# Sheet1.net
KiCad netlist of a schematic drawn in Altium Designer
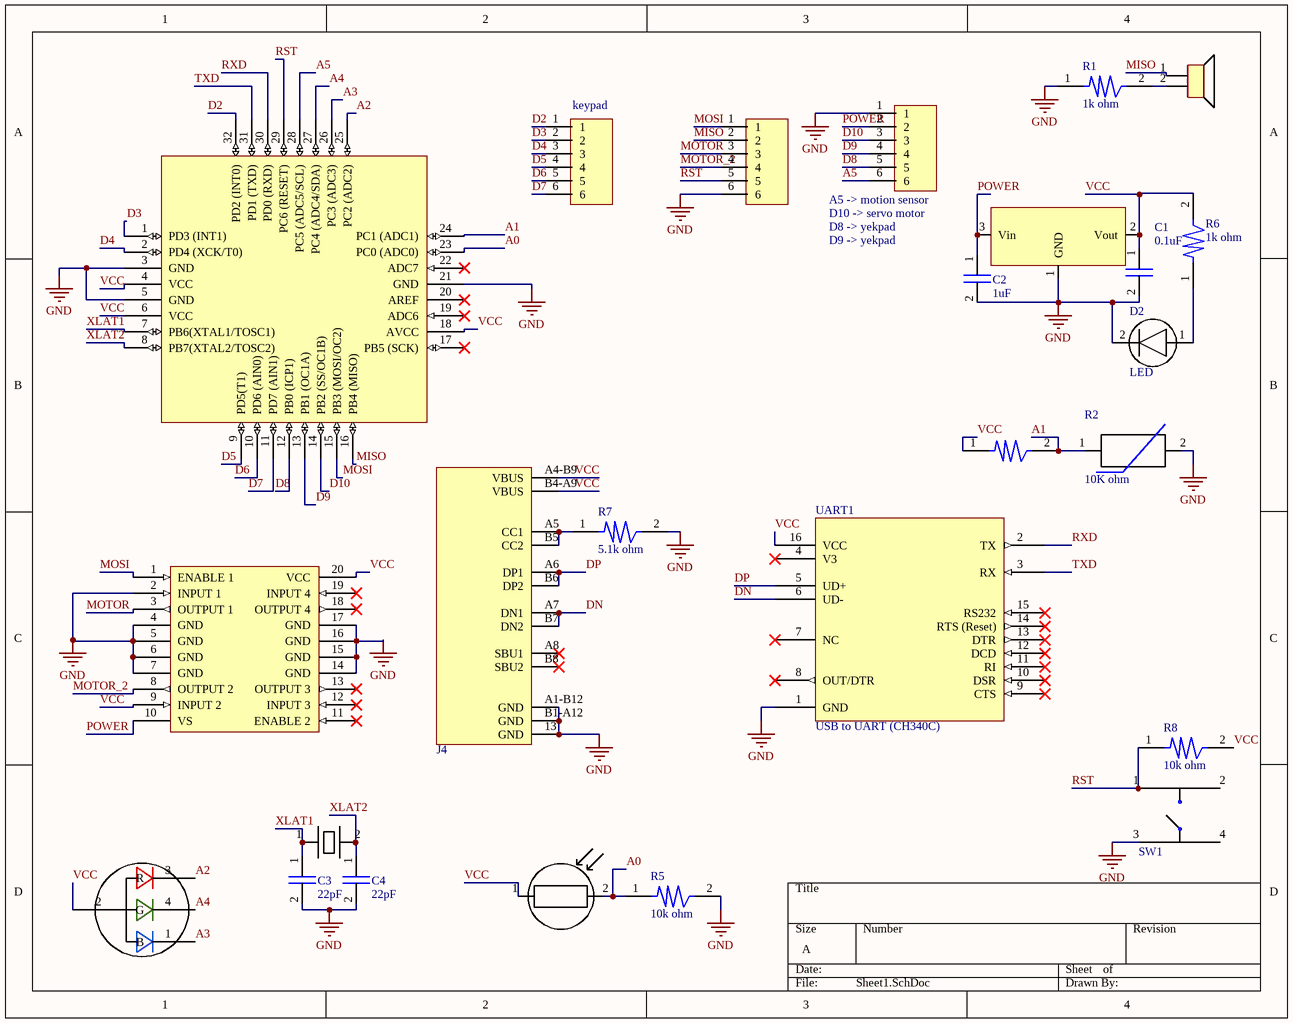
[diagram p0: Sheet1.SchDoc]

(export (version "E")
  (design (tool "Eeschema 10.0.6"))
  (components
    (comp (ref "BUZ1")
      (value "Buzzer")
      (footprint "Buzzer")
      (fields (field (name "MANUFACTURER") "Murata Electronics"))
      (libsource (lib "SCHLibrary-Badr") (part "Buzzer"))
    )
    (comp (ref "C1")
      (value "0.1uF")
      (footprint "Capacitor 0603 SMD")
      (description "50V 100nF X7R ±10% 0603 Multilayer Ceramic Capacitors MLCC - SMD/SMT ROHS")
      (fields (field (name "MANUFACTURER") "YAGEO"))
      (libsource (lib "SCHLibrary-Badr") (part "Capacitor 0.1uF"))
    )
    (comp (ref "C2")
      (value "1uF")
      (footprint "Capacitor 0603 SMD")
      (description "16V 1uF X5R ±10% 0603 Multilayer Ceramic Capacitors MLCC - SMD/SMT ROHS")
      (fields (field (name "MANUFACTURER") "Samsung Electro-Mechanics"))
      (libsource (lib "SCHLibrary-Badr") (part "Capacitor 1uF"))
    )
    (comp (ref "C3")
      (value "22pF")
      (footprint "Capacitor 0603 SMD")
      (description "50V 22pF NP0 ±5% 0603 Multilayer Ceramic Capacitors MLCC - SMD/SMT ROHS")
      (fields (field (name "MANUFACTURER") "YAGEO"))
      (libsource (lib "SCHLibrary-Badr") (part "Capacitor 22pF"))
    )
    (comp (ref "C4")
      (value "22pF")
      (footprint "Capacitor 0603 SMD")
      (description "50V 22pF NP0 ±5% 0603 Multilayer Ceramic Capacitors MLCC - SMD/SMT ROHS")
      (fields (field (name "MANUFACTURER") "YAGEO"))
      (libsource (lib "SCHLibrary-Badr") (part "Capacitor 22pF"))
    )
    (comp (ref "D1")
      (value "RGB")
      (footprint "RGB")
      (description "SMD,1.5x3mm RGB LEDs ROHS")
      (fields (field (name "MANUFACTURER") "MEIHUA") (field (name "MFR. PART #") "MHS110RGBCT"))
      (libsource (lib "Schlib_N") (part "RGB"))
    )
    (comp (ref "D2")
      (value "LED")
      (footprint "LED")
      (description "360mcd 515nm~530nm Emerald 1206 LED Indication - Discrete ROHS")
      (fields
        (field (name "MANUFACTURER") "Everlight Elec")
        (field (name "MFR. PART #") "15-21/GHC-XS1T1/3T")
      )
      (libsource (lib "Schlib_N") (part "LED"))
    )
    (comp (ref "J1")
      (value "6P 2mm Pin Headers")
      (footprint "6P 2mm Pin header")
      (description "Connector Header Through Hole 6 position 0.079\" (2.00mm)")
      (fields
        (field (name "MANUFACTURER") "TE Connectivity AMP Connectors")
        (field (name "MANUFACTURER PART NUMBER") "2355172-6")
      )
      (libsource (lib "SCHLibrary-Badr") (part "6P 2mm Pin Headers"))
    )
    (comp (ref "J2")
      (value "6P 2mm Pin Headers")
      (footprint "6P 2mm Pin header")
      (description "Connector Header Through Hole 6 position 0.079\" (2.00mm)")
      (fields
        (field (name "MANUFACTURER") "TE Connectivity AMP Connectors")
        (field (name "MANUFACTURER PART NUMBER") "2355172-6")
      )
      (libsource (lib "SCHLibrary-Badr") (part "6P 2mm Pin Headers"))
    )
    (comp (ref "J3")
      (value "6P 2mm Pin Headers")
      (footprint "6P 2mm Pin header")
      (description "Connector Header Through Hole 6 position 0.079\" (2.00mm)")
      (fields
        (field (name "MANUFACTURER") "TE Connectivity AMP Connectors")
        (field (name "MANUFACTURER PART NUMBER") "2355172-6")
      )
      (libsource (lib "SCHLibrary-Badr") (part "6P 2mm Pin Headers"))
    )
    (comp (ref "J4")
      (value "TYPE-C-31-M-12")
      (footprint "USB TYPE C-31-M-12")
      (description "5A 1 16P Female Type-C SMD USB Connectors ROHS")
      (fields (field (name "MANUFACTURER") "Korean Hroparts Elec"))
      (libsource (lib "SCHLibrary-Badr") (part "TYPE-C-31-M-12"))
    )
    (comp (ref "R1")
      (value "1k ohm")
      (footprint "Resistor 0603 SMD")
      (description "100mW Thick Film Resistors 75V ±100ppm/℃ ±1% 1kΩ 0603 Chip Resistor - Surface Mount ROHS")
      (fields (field (name "MANUFACTURER") "UNI-ROYAL(Uniroyal Elec)"))
      (libsource (lib "SCHLibrary-Badr") (part "Resistor 1k Ohm"))
    )
    (comp (ref "R2")
      (value "10K ohm")
      (footprint "Resistor 0603 SMD")
      (description "THERMISTOR NTC 10KOHM 4250K 0603")
      (fields (field (name "MANUFACTURER") "Panasonic Electronic Components"))
      (libsource (lib "SCHLibrary-Badr") (part "NTC Thermo (ERT-J1VR103J)"))
    )
    (comp (ref "R3")
      (value "10k ohm")
      (footprint "Resistor 0603 SMD")
      (description "100mW Thick Film Resistors 75V ±100ppm/℃ ±1% 10kΩ 0603 Chip Resistor - Surface Mount ROHS")
      (fields (field (name "MANUFACTURER") "UNI-ROYAL(Uniroyal Elec)"))
      (libsource (lib "SCHLibrary-Badr") (part "Resistor 10k Ohm"))
    )
    (comp (ref "R4")
      (value "Photoresistors 8kΩ~20kΩ")
      (footprint "Photoresistor GL5528")
      (description "8kΩ~20kΩ 540nm 1MΩ Plugin,P=3mm Photoresistors ROHS")
      (fields (field (name "MANUFACTURER") "Senba Sensing Tech"))
      (libsource (lib "SCHLibrary-Badr") (part "Photoresistors 8kΩ~20kΩ"))
    )
    (comp (ref "R5")
      (value "10k ohm")
      (footprint "Resistor 0603 SMD")
      (description "100mW Thick Film Resistors 75V ±100ppm/℃ ±1% 10kΩ 0603 Chip Resistor - Surface Mount ROHS")
      (fields (field (name "MANUFACTURER") "UNI-ROYAL(Uniroyal Elec)"))
      (libsource (lib "SCHLibrary-Badr") (part "Resistor 10k Ohm"))
    )
    (comp (ref "R6")
      (value "1k ohm")
      (footprint "Resistor 0603 SMD")
      (description "100mW Thick Film Resistors 75V ±100ppm/℃ ±1% 1kΩ 0603 Chip Resistor - Surface Mount ROHS")
      (fields (field (name "MANUFACTURER") "UNI-ROYAL(Uniroyal Elec)"))
      (libsource (lib "SCHLibrary-Badr") (part "Resistor 1k Ohm"))
    )
    (comp (ref "R7")
      (value "5.1k ohm")
      (footprint "Resistor 0603 SMD")
      (description "100mW Thick Film Resistors 75V ±100ppm/℃ ±1% 5.1kΩ 0603 Chip Resistor - Surface Mount ROHS")
      (fields (field (name "MANUFACTURER") "UNI-ROYAL(Uniroyal Elec)"))
      (libsource (lib "SCHLibrary-Badr") (part "Resistor 5.1k Ohm"))
    )
    (comp (ref "R8")
      (value "10k ohm")
      (footprint "Resistor 0603 SMD")
      (description "100mW Thick Film Resistors 75V ±100ppm/℃ ±1% 10kΩ 0603 Chip Resistor - Surface Mount ROHS")
      (fields (field (name "MANUFACTURER") "UNI-ROYAL(Uniroyal Elec)"))
      (libsource (lib "SCHLibrary-Badr") (part "Resistor 10k Ohm"))
    )
    (comp (ref "SW1")
      (value "Tact Switch")
      (footprint "Tact Switch")
      (description "SWITCH TACTILE SPST-NO 0.05A 12V\r\nTactile Switch SPST-NO Top Actuated Surface Mount")
      (fields (field (name "MANUFACTURER") "C&K"))
      (libsource (lib "SCHLibrary-Badr") (part "Tact Switch"))
    )
    (comp (ref "U1")
      (value "Motor_Driver")
      (footprint "L293D")
      (description "SOIC-20-300mil Stepper Motor Driver ROHS")
      (fields (field (name "MANUFACTURER") "STMicroelectronics") (field (name "MFR. PART #") "L293DD013TR"))
      (libsource (lib "Schlib_N") (part "L293D"))
    )
    (comp (ref "U2")
      (value "ATmega 8A")
      (footprint "ATmega 8A")
      (description "8KB 1KB FLASH 23 2.7V~5.5V AVR 16MHz TQFP-32(7x7) Microcontrollers (MCU/MPU/SOC) ROHS")
      (fields (field (name "MANUFACTURER") "Microchip Tech") (field (name "MFR. PART #") "ATMEGA8A-AU"))
      (libsource (lib "Schlib_N") (part "ATmega 8A"))
    )
    (comp (ref "UART1")
      (value "USB to UART (CH340C)")
      (footprint "(USB-UART) CH340C")
      (description "2Mbps Transceiver USB 2.0 SOP-16 USB Converters ROHS")
      (fields (field (name "MANUFACTURER") "WCH(Jiangsu Qin Heng)"))
      (libsource (lib "SCHLibrary-Badr") (part "USB to UART (CH340C)"))
    )
    (comp (ref "VR1")
      (value "Regulator 5V")
      (footprint "Regulator 5V AMS1117")
      (fields (field (name "MANUFACTURER") "MSKSEMI"))
      (libsource (lib "SCHLibrary-Badr") (part "Regulator 5V"))
    )
    (comp (ref "Y1")
      (value "Crystal 16Mhz")
      (footprint "Crystal 16Mhz")
      (description "16 MHz ±30ppm Crystal 20pF 50 Ohms HC-49/US")
      (fields (field (name "MANUFACTURER") "ECS Inc."))
      (libsource (lib "SCHLibrary-Badr") (part "Crystal 16Mhz"))
    )
  )
  (nets
    (net (code "1") (name "/A0") (class "Default")
      (node (ref "R4") (pin "2") (pinfunction "2_2") (pintype "passive"))
      (node (ref "R5") (pin "1") (pinfunction "1_1") (pintype "passive"))
      (node (ref "U2") (pin "23") (pinfunction "PC0_(ADC0)_23") (pintype "bidirectional"))
    )
    (net (code "2") (name "/A1") (class "Default")
      (node (ref "R2") (pin "1") (pinfunction "1_1") (pintype "passive"))
      (node (ref "R3") (pin "2") (pinfunction "2_2") (pintype "passive"))
      (node (ref "U2") (pin "24") (pinfunction "PC1_(ADC1)_24") (pintype "bidirectional"))
    )
    (net (code "3") (name "/A2") (class "Default")
      (node (ref "D1") (pin "3") (pinfunction "R_3") (pintype "passive"))
      (node (ref "U2") (pin "25") (pinfunction "PC2_(ADC2)_25") (pintype "bidirectional"))
    )
    (net (code "4") (name "/A3") (class "Default")
      (node (ref "D1") (pin "1") (pinfunction "B_1") (pintype "passive"))
      (node (ref "U2") (pin "26") (pinfunction "PC3_(ADC3)_26") (pintype "bidirectional"))
    )
    (net (code "5") (name "/A4") (class "Default")
      (node (ref "D1") (pin "4") (pinfunction "G_4") (pintype "passive"))
      (node (ref "U2") (pin "27") (pinfunction "PC4_(ADC4/SDA)_27") (pintype "bidirectional"))
    )
    (net (code "6") (name "/A5") (class "Default")
      (node (ref "J1") (pin "6") (pinfunction "6_6") (pintype "passive"))
      (node (ref "U2") (pin "28") (pinfunction "PC5_(ADC5/SCL)_28") (pintype "bidirectional"))
    )
    (net (code "7") (name "/D2") (class "Default")
      (node (ref "J3") (pin "1") (pinfunction "1_1") (pintype "passive"))
      (node (ref "U2") (pin "32") (pinfunction "PD2_(INT0)_32") (pintype "bidirectional"))
    )
    (net (code "8") (name "/D3") (class "Default")
      (node (ref "J3") (pin "2") (pinfunction "2_2") (pintype "passive"))
      (node (ref "U2") (pin "1") (pinfunction "PD3_(INT1)_1") (pintype "bidirectional"))
    )
    (net (code "9") (name "/D4") (class "Default")
      (node (ref "J3") (pin "3") (pinfunction "3_3") (pintype "passive"))
      (node (ref "U2") (pin "2") (pinfunction "PD4_(XCK/T0)_2") (pintype "bidirectional"))
    )
    (net (code "10") (name "/D5") (class "Default")
      (node (ref "J3") (pin "4") (pinfunction "4_4") (pintype "passive"))
      (node (ref "U2") (pin "9") (pinfunction "PD5(T1)_9") (pintype "bidirectional"))
    )
    (net (code "11") (name "/D6") (class "Default")
      (node (ref "J3") (pin "5") (pinfunction "5_5") (pintype "passive"))
      (node (ref "U2") (pin "10") (pinfunction "PD6_(AIN0)_10") (pintype "bidirectional"))
    )
    (net (code "12") (name "/D7") (class "Default")
      (node (ref "J3") (pin "6") (pinfunction "6_6") (pintype "passive"))
      (node (ref "U2") (pin "11") (pinfunction "PD7_(AIN1)_11") (pintype "bidirectional"))
    )
    (net (code "13") (name "/D8") (class "Default")
      (node (ref "J1") (pin "5") (pinfunction "5_5") (pintype "passive"))
      (node (ref "U2") (pin "12") (pinfunction "PB0_(ICP1)_12") (pintype "bidirectional"))
    )
    (net (code "14") (name "/D9") (class "Default")
      (node (ref "J1") (pin "4") (pinfunction "4_4") (pintype "passive"))
      (node (ref "U2") (pin "13") (pinfunction "PB1_(OC1A)_13") (pintype "bidirectional"))
    )
    (net (code "15") (name "/D10") (class "Default")
      (node (ref "J1") (pin "3") (pinfunction "3_3") (pintype "passive"))
      (node (ref "U2") (pin "14") (pinfunction "PB2_(SS/OC1B)_14") (pintype "bidirectional"))
    )
    (net (code "16") (name "/DN") (class "Default")
      (node (ref "J4") (pin "A7") (pinfunction "DN1_A7") (pintype "passive"))
      (node (ref "J4") (pin "B7") (pinfunction "DN2_B7") (pintype "passive"))
      (node (ref "UART1") (pin "6") (pinfunction "UD-_6") (pintype "passive"))
    )
    (net (code "17") (name "/DP") (class "Default")
      (node (ref "J4") (pin "A6") (pinfunction "DP1_A6") (pintype "passive"))
      (node (ref "J4") (pin "B6") (pinfunction "DP2_B6") (pintype "passive"))
      (node (ref "UART1") (pin "5") (pinfunction "UD+_5") (pintype "passive"))
    )
    (net (code "18") (name "/MISO") (class "Default")
      (node (ref "BUZ1") (pin "1") (pinfunction "1_1") (pintype "passive"))
      (node (ref "J2") (pin "2") (pinfunction "2_2") (pintype "passive"))
      (node (ref "U2") (pin "16") (pinfunction "PB4_(MISO)_16") (pintype "bidirectional"))
    )
    (net (code "19") (name "/MOSI") (class "Default")
      (node (ref "J2") (pin "1") (pinfunction "1_1") (pintype "passive"))
      (node (ref "U1") (pin "1") (pinfunction "ENABLE_1_1") (pintype "input"))
      (node (ref "U2") (pin "15") (pinfunction "PB3_(MOSI/OC2)_15") (pintype "bidirectional"))
    )
    (net (code "20") (name "/MOTOR") (class "Default")
      (node (ref "J2") (pin "3") (pinfunction "3_3") (pintype "passive"))
      (node (ref "U1") (pin "3") (pinfunction "OUTPUT_1_3") (pintype "output"))
    )
    (net (code "21") (name "/MOTOR_2") (class "Default")
      (node (ref "J2") (pin "4") (pinfunction "4_4") (pintype "passive"))
      (node (ref "U1") (pin "8") (pinfunction "OUTPUT_2_8") (pintype "output"))
    )
    (net (code "22") (name "/POWER") (class "Default")
      (node (ref "C2") (pin "1") (pinfunction "1_1") (pintype "passive"))
      (node (ref "J1") (pin "2") (pinfunction "2_2") (pintype "passive"))
      (node (ref "U1") (pin "10") (pinfunction "VS_10") (pintype "passive"))
      (node (ref "VR1") (pin "3") (pinfunction "Vin_3") (pintype "passive"))
    )
    (net (code "23") (name "/RST") (class "Default")
      (node (ref "J2") (pin "5") (pinfunction "5_5") (pintype "passive"))
      (node (ref "R8") (pin "1") (pinfunction "1_1") (pintype "passive"))
      (node (ref "SW1") (pin "1") (pinfunction "1_1") (pintype "passive"))
      (node (ref "U2") (pin "29") (pinfunction "PC6_(RESET)_29") (pintype "bidirectional"))
    )
    (net (code "24") (name "/RXD") (class "Default")
      (node (ref "U2") (pin "30") (pinfunction "PD0_(RXD)_30") (pintype "bidirectional"))
      (node (ref "UART1") (pin "2") (pinfunction "TX_2") (pintype "output"))
    )
    (net (code "25") (name "/TXD") (class "Default")
      (node (ref "U2") (pin "31") (pinfunction "PD1_(TXD)_31") (pintype "bidirectional"))
      (node (ref "UART1") (pin "3") (pinfunction "RX_3") (pintype "input"))
    )
    (net (code "26") (name "/VCC") (class "Default")
      (node (ref "C1") (pin "1") (pinfunction "1_1") (pintype "passive"))
      (node (ref "D1") (pin "2") (pinfunction "Anode_2") (pintype "passive"))
      (node (ref "J4") (pin "A4-B9") (pinfunction "VBUS_A4-B9") (pintype "passive"))
      (node (ref "J4") (pin "B4-A9") (pinfunction "VBUS_B4-A9") (pintype "passive"))
      (node (ref "R3") (pin "1") (pinfunction "1_1") (pintype "passive"))
      (node (ref "R4") (pin "1") (pinfunction "1_1") (pintype "passive"))
      (node (ref "R6") (pin "2") (pinfunction "2_2") (pintype "passive"))
      (node (ref "R8") (pin "2") (pinfunction "2_2") (pintype "passive"))
      (node (ref "U1") (pin "20") (pinfunction "VCC_20") (pintype "passive"))
      (node (ref "U1") (pin "9") (pinfunction "INPUT_2_9") (pintype "input"))
      (node (ref "U2") (pin "18") (pinfunction "AVCC_18") (pintype "passive"))
      (node (ref "U2") (pin "4") (pinfunction "VCC_4") (pintype "passive"))
      (node (ref "U2") (pin "6") (pinfunction "VCC_6") (pintype "passive"))
      (node (ref "UART1") (pin "16") (pinfunction "VCC_16") (pintype "passive"))
      (node (ref "VR1") (pin "2") (pinfunction "Vout_2") (pintype "passive"))
    )
    (net (code "27") (name "/XLAT1") (class "Default")
      (node (ref "C3") (pin "1") (pinfunction "1_1") (pintype "passive"))
      (node (ref "U2") (pin "7") (pinfunction "PB6(XTAL1/TOSC1)_7") (pintype "bidirectional"))
      (node (ref "Y1") (pin "1") (pinfunction "1_1") (pintype "passive"))
    )
    (net (code "28") (name "/XLAT2") (class "Default")
      (node (ref "C4") (pin "1") (pinfunction "1_1") (pintype "passive"))
      (node (ref "U2") (pin "8") (pinfunction "PB7(XTAL2/TOSC2)_8") (pintype "bidirectional"))
      (node (ref "Y1") (pin "2") (pinfunction "2_2") (pintype "passive"))
    )
    (net (code "29") (name "GND") (class "Default")
      (node (ref "C1") (pin "2") (pinfunction "2_2") (pintype "passive"))
      (node (ref "C2") (pin "2") (pinfunction "2_2") (pintype "passive"))
      (node (ref "C3") (pin "2") (pinfunction "2_2") (pintype "passive"))
      (node (ref "C4") (pin "2") (pinfunction "2_2") (pintype "passive"))
      (node (ref "D2") (pin "2") (pinfunction "2_2") (pintype "passive"))
      (node (ref "J1") (pin "1") (pinfunction "1_1") (pintype "passive"))
      (node (ref "J2") (pin "6") (pinfunction "6_6") (pintype "passive"))
      (node (ref "J4") (pin "13") (pinfunction "GND_13") (pintype "passive"))
      (node (ref "J4") (pin "A1-B12") (pinfunction "GND_A1-B12") (pintype "passive"))
      (node (ref "J4") (pin "B1-A12") (pinfunction "GND_B1-A12") (pintype "passive"))
      (node (ref "R1") (pin "1") (pinfunction "1_1") (pintype "passive"))
      (node (ref "R2") (pin "2") (pinfunction "2_2") (pintype "passive"))
      (node (ref "R5") (pin "2") (pinfunction "2_2") (pintype "passive"))
      (node (ref "R7") (pin "2") (pinfunction "2_2") (pintype "passive"))
      (node (ref "SW1") (pin "3") (pinfunction "3_3") (pintype "passive"))
      (node (ref "U1") (pin "14") (pinfunction "GND_14") (pintype "passive"))
      (node (ref "U1") (pin "15") (pinfunction "GND_15") (pintype "passive"))
      (node (ref "U1") (pin "16") (pinfunction "GND_16") (pintype "passive"))
      (node (ref "U1") (pin "17") (pinfunction "GND_17") (pintype "passive"))
      (node (ref "U1") (pin "2") (pinfunction "INPUT_1_2") (pintype "input"))
      (node (ref "U1") (pin "4") (pinfunction "GND_4") (pintype "passive"))
      (node (ref "U1") (pin "5") (pinfunction "GND_5") (pintype "passive"))
      (node (ref "U1") (pin "6") (pinfunction "GND_6") (pintype "passive"))
      (node (ref "U1") (pin "7") (pinfunction "GND_7") (pintype "passive"))
      (node (ref "U2") (pin "21") (pinfunction "GND_21") (pintype "passive"))
      (node (ref "U2") (pin "3") (pinfunction "GND_3") (pintype "passive"))
      (node (ref "U2") (pin "5") (pinfunction "GND_5") (pintype "passive"))
      (node (ref "UART1") (pin "1") (pinfunction "GND_1") (pintype "passive"))
      (node (ref "VR1") (pin "1") (pinfunction "GND_1") (pintype "passive"))
    )
    (net (code "30") (name "Net-(BUZ1-Pad2)") (class "Default")
      (node (ref "BUZ1") (pin "2") (pinfunction "2_2") (pintype "passive"))
      (node (ref "R1") (pin "2") (pinfunction "2_2") (pintype "passive"))
    )
    (net (code "31") (name "Net-(D2-Pad1)") (class "Default")
      (node (ref "D2") (pin "1") (pinfunction "1_1") (pintype "passive"))
      (node (ref "R6") (pin "1") (pinfunction "1_1") (pintype "passive"))
    )
    (net (code "32") (name "Net-(J4-CC1)") (class "Default")
      (node (ref "J4") (pin "A5") (pinfunction "CC1_A5") (pintype "passive"))
      (node (ref "J4") (pin "B5") (pinfunction "CC2_B5") (pintype "passive"))
      (node (ref "R7") (pin "1") (pinfunction "1_1") (pintype "passive"))
    )
    (net (code "33") (name "unconnected-(J4-SBU1-PadA8)") (class "Default")
      (node (ref "J4") (pin "A8") (pinfunction "SBU1_A8") (pintype "passive+no_connect"))
    )
    (net (code "34") (name "unconnected-(J4-SBU2-PadB8)") (class "Default")
      (node (ref "J4") (pin "B8") (pinfunction "SBU2_B8") (pintype "passive+no_connect"))
    )
    (net (code "35") (name "unconnected-(SW1-Pad2)") (class "Default")
      (node (ref "SW1") (pin "2") (pinfunction "2_2") (pintype "passive"))
    )
    (net (code "36") (name "unconnected-(SW1-Pad4)") (class "Default")
      (node (ref "SW1") (pin "4") (pinfunction "4_4") (pintype "passive"))
    )
    (net (code "37") (name "unconnected-(U1-ENABLE_2-Pad11)") (class "Default")
      (node (ref "U1") (pin "11") (pinfunction "ENABLE_2_11") (pintype "input+no_connect"))
    )
    (net (code "38") (name "unconnected-(U1-INPUT_3-Pad12)") (class "Default")
      (node (ref "U1") (pin "12") (pinfunction "INPUT_3_12") (pintype "input+no_connect"))
    )
    (net (code "39") (name "unconnected-(U1-INPUT_4-Pad19)") (class "Default")
      (node (ref "U1") (pin "19") (pinfunction "INPUT_4_19") (pintype "input+no_connect"))
    )
    (net (code "40") (name "unconnected-(U1-OUTPUT_3-Pad13)") (class "Default")
      (node (ref "U1") (pin "13") (pinfunction "OUTPUT_3_13") (pintype "output+no_connect"))
    )
    (net (code "41") (name "unconnected-(U1-OUTPUT_4-Pad18)") (class "Default")
      (node (ref "U1") (pin "18") (pinfunction "OUTPUT_4_18") (pintype "output+no_connect"))
    )
    (net (code "42") (name "unconnected-(U2-ADC6-Pad19)") (class "Default")
      (node (ref "U2") (pin "19") (pinfunction "ADC6_19") (pintype "input+no_connect"))
    )
    (net (code "43") (name "unconnected-(U2-ADC7-Pad22)") (class "Default")
      (node (ref "U2") (pin "22") (pinfunction "ADC7_22") (pintype "input+no_connect"))
    )
    (net (code "44") (name "unconnected-(U2-AREF-Pad20)") (class "Default")
      (node (ref "U2") (pin "20") (pinfunction "AREF_20") (pintype "passive+no_connect"))
    )
    (net (code "45") (name "unconnected-(U2-PB5_(SCK)-Pad17)") (class "Default")
      (node (ref "U2") (pin "17") (pinfunction "PB5_(SCK)_17") (pintype "bidirectional+no_connect"))
    )
    (net (code "46") (name "unconnected-(UART1-CTS-Pad9)") (class "Default")
      (node (ref "UART1") (pin "9") (pinfunction "CTS_9") (pintype "input+no_connect"))
    )
    (net (code "47") (name "unconnected-(UART1-DCD-Pad12)") (class "Default")
      (node (ref "UART1") (pin "12") (pinfunction "DCD_12") (pintype "input+no_connect"))
    )
    (net (code "48") (name "unconnected-(UART1-DSR-Pad10)") (class "Default")
      (node (ref "UART1") (pin "10") (pinfunction "DSR_10") (pintype "input+no_connect"))
    )
    (net (code "49") (name "unconnected-(UART1-DTR-Pad13)") (class "Default")
      (node (ref "UART1") (pin "13") (pinfunction "DTR_13") (pintype "output+no_connect"))
    )
    (net (code "50") (name "unconnected-(UART1-NC-Pad7)") (class "Default")
      (node (ref "UART1") (pin "7") (pinfunction "NC_7") (pintype "passive+no_connect"))
    )
    (net (code "51") (name "unconnected-(UART1-OUT{slash}DTR-Pad8)") (class "Default")
      (node (ref "UART1") (pin "8") (pinfunction "OUT/DTR_8") (pintype "output+no_connect"))
    )
    (net (code "52") (name "unconnected-(UART1-RI-Pad11)") (class "Default")
      (node (ref "UART1") (pin "11") (pinfunction "RI_11") (pintype "input+no_connect"))
    )
    (net (code "53") (name "unconnected-(UART1-RS232-Pad15)") (class "Default")
      (node (ref "UART1") (pin "15") (pinfunction "RS232_15") (pintype "input+no_connect"))
    )
    (net (code "54") (name "unconnected-(UART1-RTS_(Reset)-Pad14)") (class "Default")
      (node (ref "UART1") (pin "14") (pinfunction "RTS_(Reset)_14") (pintype "output+no_connect"))
    )
    (net (code "55") (name "unconnected-(UART1-V3-Pad4)") (class "Default")
      (node (ref "UART1") (pin "4") (pinfunction "V3_4") (pintype "passive+no_connect"))
    )
  )
)
